# SolidStateTeslaCoil_GateCoilDriver_SCHEM.net
KiCad netlist of a schematic drawn in Altium Designer
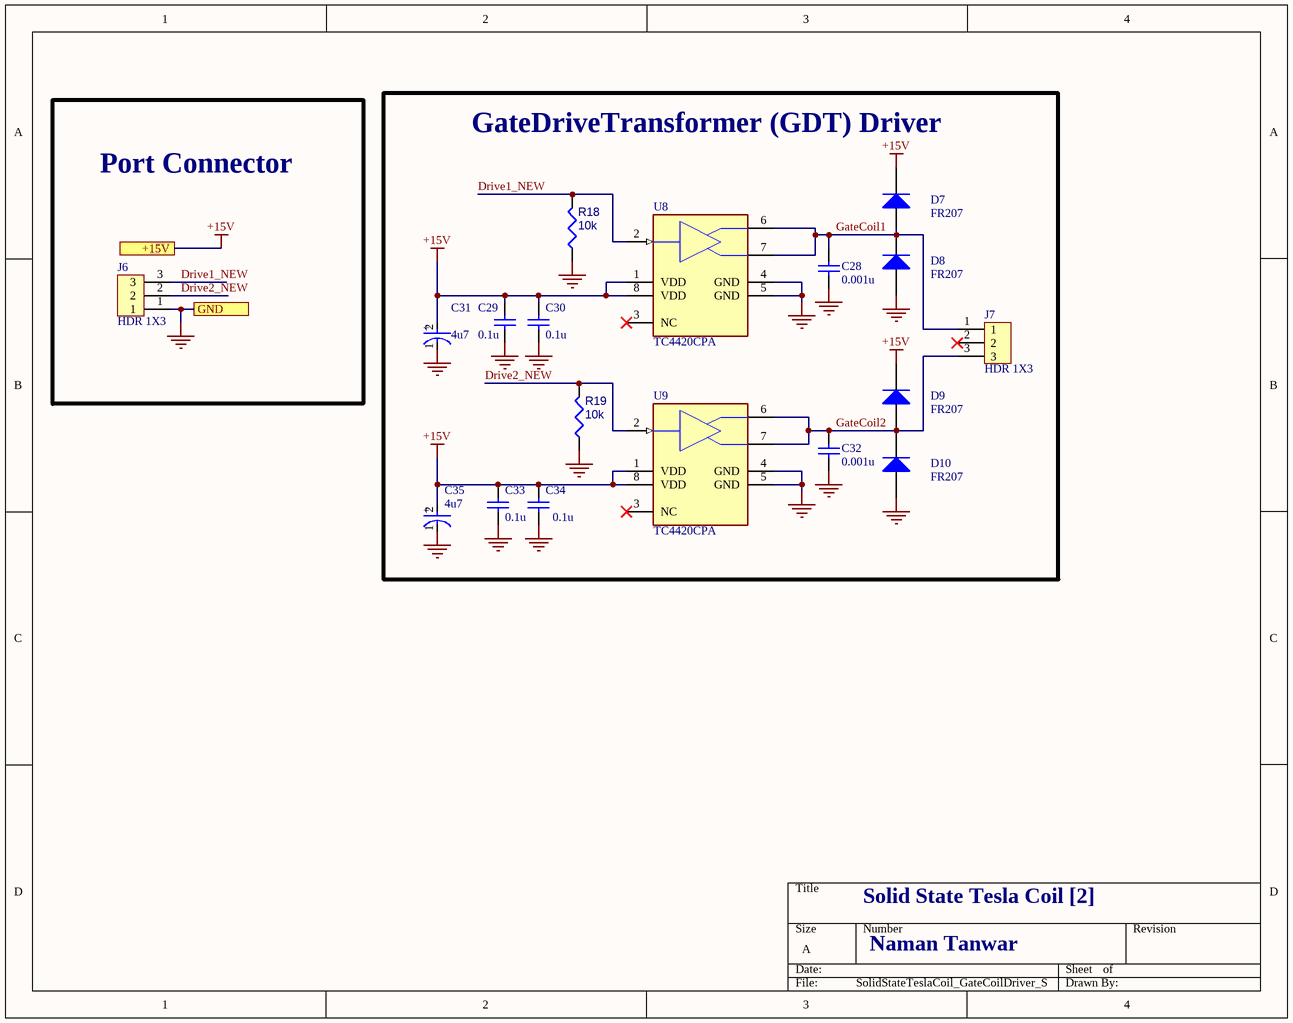
[diagram p0: SolidStateTeslaCoil_GateCoilDriver_SCHEMATIC.SchDoc]

(export (version "E")
  (design (tool "Eeschema 10.0.6"))
  (components
    (comp (ref "C28")
      (value "0.001u")
      (footprint "Ceramic Capacitor THT")
      (description "Ceramic Capacitor, 1 nF, +/- 10%, 50 V, -55 to 125 degC, 2-Pin THD, RoHS, Tape and Reel")
      (fields (field (name "MANUFACTURER") "Vishay") (field (name "TOLERANCE") "±10%"))
      (libsource (lib "SolidStateTeslaCoilSCHLIB") (part "0.001u 102 Ceramic Capacitor"))
    )
    (comp (ref "C29")
      (value "0.1u")
      (footprint "Ceramic Capacitor THT")
      (description "Ceramic Capacitor, 100 nF, +/- 10%, 50 V, -55 to 125 degC, 2-Pin THD, RoHS, Tape and Reel")
      (fields (field (name "MANUFACTURER") "Vishay") (field (name "TOLERANCE") "±10%"))
      (libsource (lib "SolidStateTeslaCoilSCHLIB") (part "0.1u 104 Ceramic Capacitor"))
    )
    (comp (ref "C30")
      (value "0.1u")
      (footprint "Ceramic Capacitor THT")
      (description "Ceramic Capacitor, 100 nF, +/- 10%, 50 V, -55 to 125 degC, 2-Pin THD, RoHS, Tape and Reel")
      (fields (field (name "MANUFACTURER") "Vishay") (field (name "TOLERANCE") "±10%"))
      (libsource (lib "SolidStateTeslaCoilSCHLIB") (part "0.1u 104 Ceramic Capacitor"))
    )
    (comp (ref "C31")
      (value "4u7")
      (footprint "FP-RAD-TH-D_5_0_5-L_11_1-MFG")
      (description "Aluminum Electrolytic Capacitors (Radial Lead Type) AEC-Q200 Qualified 4u7uF ±20% 50V")
      (fields (field (name "TOLERANCE") "20%"))
      (libsource (lib "SolidStateTeslaCoilSCHLIB") (part "4u7 Electrolytic Capacitor"))
    )
    (comp (ref "C32")
      (value "0.001u")
      (footprint "Ceramic Capacitor THT")
      (description "Ceramic Capacitor, 1 nF, +/- 10%, 50 V, -55 to 125 degC, 2-Pin THD, RoHS, Tape and Reel")
      (fields (field (name "MANUFACTURER") "Vishay") (field (name "TOLERANCE") "±10%"))
      (libsource (lib "SolidStateTeslaCoilSCHLIB") (part "0.001u 102 Ceramic Capacitor"))
    )
    (comp (ref "C33")
      (value "0.1u")
      (footprint "Ceramic Capacitor THT")
      (description "Ceramic Capacitor, 100 nF, +/- 10%, 50 V, -55 to 125 degC, 2-Pin THD, RoHS, Tape and Reel")
      (fields (field (name "MANUFACTURER") "Vishay") (field (name "TOLERANCE") "±10%"))
      (libsource (lib "SolidStateTeslaCoilSCHLIB") (part "0.1u 104 Ceramic Capacitor"))
    )
    (comp (ref "C34")
      (value "0.1u")
      (footprint "Ceramic Capacitor THT")
      (description "Ceramic Capacitor, 100 nF, +/- 10%, 50 V, -55 to 125 degC, 2-Pin THD, RoHS, Tape and Reel")
      (fields (field (name "MANUFACTURER") "Vishay") (field (name "TOLERANCE") "±10%"))
      (libsource (lib "SolidStateTeslaCoilSCHLIB") (part "0.1u 104 Ceramic Capacitor"))
    )
    (comp (ref "C35")
      (value "4u7")
      (footprint "FP-RAD-TH-D_5_0_5-L_11_1-MFG")
      (description "Aluminum Electrolytic Capacitors (Radial Lead Type) AEC-Q200 Qualified 4u7uF ±20% 50V")
      (fields (field (name "TOLERANCE") "20%"))
      (libsource (lib "SolidStateTeslaCoilSCHLIB") (part "4u7 Electrolytic Capacitor"))
    )
    (comp (ref "D7")
      (value "FR207")
      (footprint "Diode")
      (fields (field (name "MANUFACTURER") "Multicomp"))
      (libsource (lib "SolidStateTeslaCoilSCHLIB") (part "FR207"))
    )
    (comp (ref "D8")
      (value "FR207")
      (footprint "Diode")
      (fields (field (name "MANUFACTURER") "Multicomp"))
      (libsource (lib "SolidStateTeslaCoilSCHLIB") (part "FR207"))
    )
    (comp (ref "D9")
      (value "FR207")
      (footprint "Diode")
      (fields (field (name "MANUFACTURER") "Multicomp"))
      (libsource (lib "SolidStateTeslaCoilSCHLIB") (part "FR207"))
    )
    (comp (ref "D10")
      (value "FR207")
      (footprint "Diode")
      (fields (field (name "MANUFACTURER") "Multicomp"))
      (libsource (lib "SolidStateTeslaCoilSCHLIB") (part "FR207"))
    )
    (comp (ref "J6")
      (value "HDR 1X3")
      (footprint "HDR_1x3_2.54mm")
      (description "Conn Unshrouded Header HDR 3 POS 2.54mm Solder ST Top Entry Thru-Hole BergStik® Automotive Bulk")
      (fields
        (field (name "MANUFACTURER") "Amphenol ICC / FCI")
        (field (name "MANUFACTURER PART NUMBER") "68000-103HLF")
      )
      (libsource (lib "SolidStateTeslaCoilSCHLIB") (part "68000-103HLF"))
    )
    (comp (ref "J7")
      (value "HDR 1X3")
      (footprint "HDR_1x3_2.54mm")
      (description "Conn Unshrouded Header HDR 3 POS 2.54mm Solder ST Top Entry Thru-Hole BergStik® Automotive Bulk")
      (fields
        (field (name "MANUFACTURER") "Amphenol ICC / FCI")
        (field (name "MANUFACTURER PART NUMBER") "68000-103HLF")
      )
      (libsource (lib "") (part "68000-103HLF_1"))
    )
    (comp (ref "R18")
      (value "10k")
      (footprint "RESA60-630X240")
      (description "Axial Resistor, 10 KOhm, +/- 1%, 250 mW, -55 to 155 degC, 2-Pin THD, RoHS, Bulk")
      (libsource (lib "SolidStateTeslaCoilSCHLIB") (part "10k"))
    )
    (comp (ref "R19")
      (value "10k")
      (footprint "RESA60-630X240")
      (description "Axial Resistor, 10 KOhm, +/- 1%, 250 mW, -55 to 155 degC, 2-Pin THD, RoHS, Bulk")
      (libsource (lib "SolidStateTeslaCoilSCHLIB") (part "10k"))
    )
    (comp (ref "U8")
      (value "TC4420CPA")
      (footprint "8PinDIP")
      (description "6A High-Speed MOSFET Driver, Non-Inverting, Commercial Temperature")
      (libsource (lib "SolidStateTeslaCoilSCHLIB") (part "TC4420"))
    )
    (comp (ref "U9")
      (value "TC4420CPA")
      (footprint "8PinDIP")
      (description "6A High-Speed MOSFET Driver, Non-Inverting, Commercial Temperature")
      (libsource (lib "SolidStateTeslaCoilSCHLIB") (part "TC4420"))
    )
  )
  (nets
    (net (code "1") (name "+15V") (class "Default")
      (node (ref "C29") (pin "2") (pinfunction "2_2") (pintype "passive"))
      (node (ref "C30") (pin "2") (pinfunction "2_2") (pintype "passive"))
      (node (ref "C31") (pin "2") (pinfunction "A_2") (pintype "passive"))
      (node (ref "C33") (pin "2") (pinfunction "2_2") (pintype "passive"))
      (node (ref "C34") (pin "2") (pinfunction "2_2") (pintype "passive"))
      (node (ref "C35") (pin "2") (pinfunction "A_2") (pintype "passive"))
      (node (ref "D7") (pin "2") (pinfunction "K_2") (pintype "passive"))
      (node (ref "D9") (pin "2") (pinfunction "K_2") (pintype "passive"))
      (node (ref "U8") (pin "1") (pinfunction "VDD_1") (pintype "power_in"))
      (node (ref "U8") (pin "8") (pinfunction "VDD_8") (pintype "power_in"))
      (node (ref "U9") (pin "1") (pinfunction "VDD_1") (pintype "power_in"))
      (node (ref "U9") (pin "8") (pinfunction "VDD_8") (pintype "power_in"))
    )
    (net (code "2") (name "/Drive1_NEW") (class "Default")
      (node (ref "J6") (pin "3") (pinfunction "3_3") (pintype "passive"))
      (node (ref "R18") (pin "2") (pinfunction "2_2") (pintype "passive"))
      (node (ref "U8") (pin "2") (pinfunction "IN_2") (pintype "input"))
    )
    (net (code "3") (name "/Drive2_NEW") (class "Default")
      (node (ref "J6") (pin "2") (pinfunction "2_2") (pintype "passive"))
      (node (ref "R19") (pin "2") (pinfunction "2_2") (pintype "passive"))
      (node (ref "U9") (pin "2") (pinfunction "IN_2") (pintype "input"))
    )
    (net (code "4") (name "/GateCoil1") (class "Default")
      (node (ref "C28") (pin "2") (pinfunction "2_2") (pintype "passive"))
      (node (ref "D7") (pin "1") (pinfunction "A_1") (pintype "passive"))
      (node (ref "D8") (pin "2") (pinfunction "K_2") (pintype "passive"))
      (node (ref "J7") (pin "1") (pinfunction "1_1") (pintype "passive"))
      (node (ref "U8") (pin "6") (pinfunction "OUT_6") (pintype "tri_state"))
      (node (ref "U8") (pin "7") (pinfunction "OUT_7") (pintype "tri_state"))
    )
    (net (code "5") (name "/GateCoil2") (class "Default")
      (node (ref "C32") (pin "2") (pinfunction "2_2") (pintype "passive"))
      (node (ref "D10") (pin "2") (pinfunction "K_2") (pintype "passive"))
      (node (ref "D9") (pin "1") (pinfunction "A_1") (pintype "passive"))
      (node (ref "J7") (pin "3") (pinfunction "3_3") (pintype "passive"))
      (node (ref "U9") (pin "6") (pinfunction "OUT_6") (pintype "tri_state"))
      (node (ref "U9") (pin "7") (pinfunction "OUT_7") (pintype "tri_state"))
    )
    (net (code "6") (name "GND") (class "Default")
      (node (ref "C28") (pin "1") (pinfunction "1_1") (pintype "passive"))
      (node (ref "C29") (pin "1") (pinfunction "1_1") (pintype "passive"))
      (node (ref "C30") (pin "1") (pinfunction "1_1") (pintype "passive"))
      (node (ref "C31") (pin "1") (pinfunction "C_1") (pintype "passive"))
      (node (ref "C32") (pin "1") (pinfunction "1_1") (pintype "passive"))
      (node (ref "C33") (pin "1") (pinfunction "1_1") (pintype "passive"))
      (node (ref "C34") (pin "1") (pinfunction "1_1") (pintype "passive"))
      (node (ref "C35") (pin "1") (pinfunction "C_1") (pintype "passive"))
      (node (ref "D10") (pin "1") (pinfunction "A_1") (pintype "passive"))
      (node (ref "D8") (pin "1") (pinfunction "A_1") (pintype "passive"))
      (node (ref "J6") (pin "1") (pinfunction "1_1") (pintype "passive"))
      (node (ref "R18") (pin "1") (pinfunction "1_1") (pintype "passive"))
      (node (ref "R19") (pin "1") (pinfunction "1_1") (pintype "passive"))
      (node (ref "U8") (pin "4") (pinfunction "GND_4") (pintype "power_in"))
      (node (ref "U8") (pin "5") (pinfunction "GND_5") (pintype "power_in"))
      (node (ref "U9") (pin "4") (pinfunction "GND_4") (pintype "power_in"))
      (node (ref "U9") (pin "5") (pinfunction "GND_5") (pintype "power_in"))
    )
    (net (code "7") (name "unconnected-(J7-Pad2)") (class "Default")
      (node (ref "J7") (pin "2") (pinfunction "2_2") (pintype "passive+no_connect"))
    )
    (net (code "8") (name "unconnected-(U8-NC-Pad3)") (class "Default")
      (node (ref "U8") (pin "3") (pinfunction "NC_3") (pintype "passive+no_connect"))
    )
    (net (code "9") (name "unconnected-(U9-NC-Pad3)") (class "Default")
      (node (ref "U9") (pin "3") (pinfunction "NC_3") (pintype "passive+no_connect"))
    )
  )
)
